# LED_Strip.net
KiCad netlist of a schematic drawn in Altium Designer
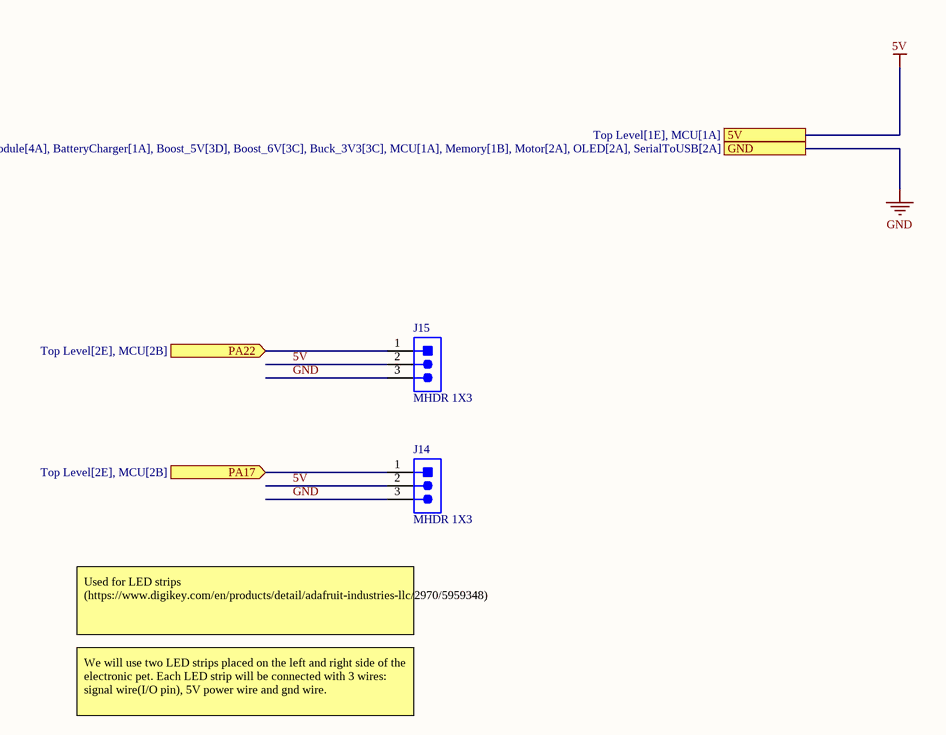
[diagram p0: LED Strip.SchDoc]

(export (version "E")
  (design (tool "Eeschema 10.0.6"))
  (components
    (comp (ref "J14")
      (value "MHDR 1X3")
      (footprint "PH1-03-UA WITH CONNECTOR")
      (description "Header, 3-Pin, 0.1in Pitch, Male")
      (libsource (lib "University of Pennsylvania (ESE)") (part "Header 1X3"))
    )
    (comp (ref "J15")
      (value "MHDR 1X3")
      (footprint "PH1-03-UA WITH CONNECTOR")
      (description "Header, 3-Pin, 0.1in Pitch, Male")
      (libsource (lib "University of Pennsylvania (ESE)") (part "Header 1X3"))
    )
  )
  (nets
    (net (code "1") (name "/PA17") (class "Default")
      (node (ref "J14") (pin "1") (pinfunction "1_1") (pintype "passive"))
    )
    (net (code "2") (name "/PA22") (class "Default")
      (node (ref "J15") (pin "1") (pinfunction "1_1") (pintype "passive"))
    )
    (net (code "3") (name "5V") (class "Default")
      (node (ref "J14") (pin "2") (pinfunction "2_2") (pintype "passive"))
      (node (ref "J15") (pin "2") (pinfunction "2_2") (pintype "passive"))
    )
    (net (code "4") (name "GND") (class "Default")
      (node (ref "J14") (pin "3") (pinfunction "3_3") (pintype "passive"))
      (node (ref "J15") (pin "3") (pinfunction "3_3") (pintype "passive"))
    )
  )
)
